# LevelShiftDAC.net
KiCad netlist of a schematic drawn in Altium Designer
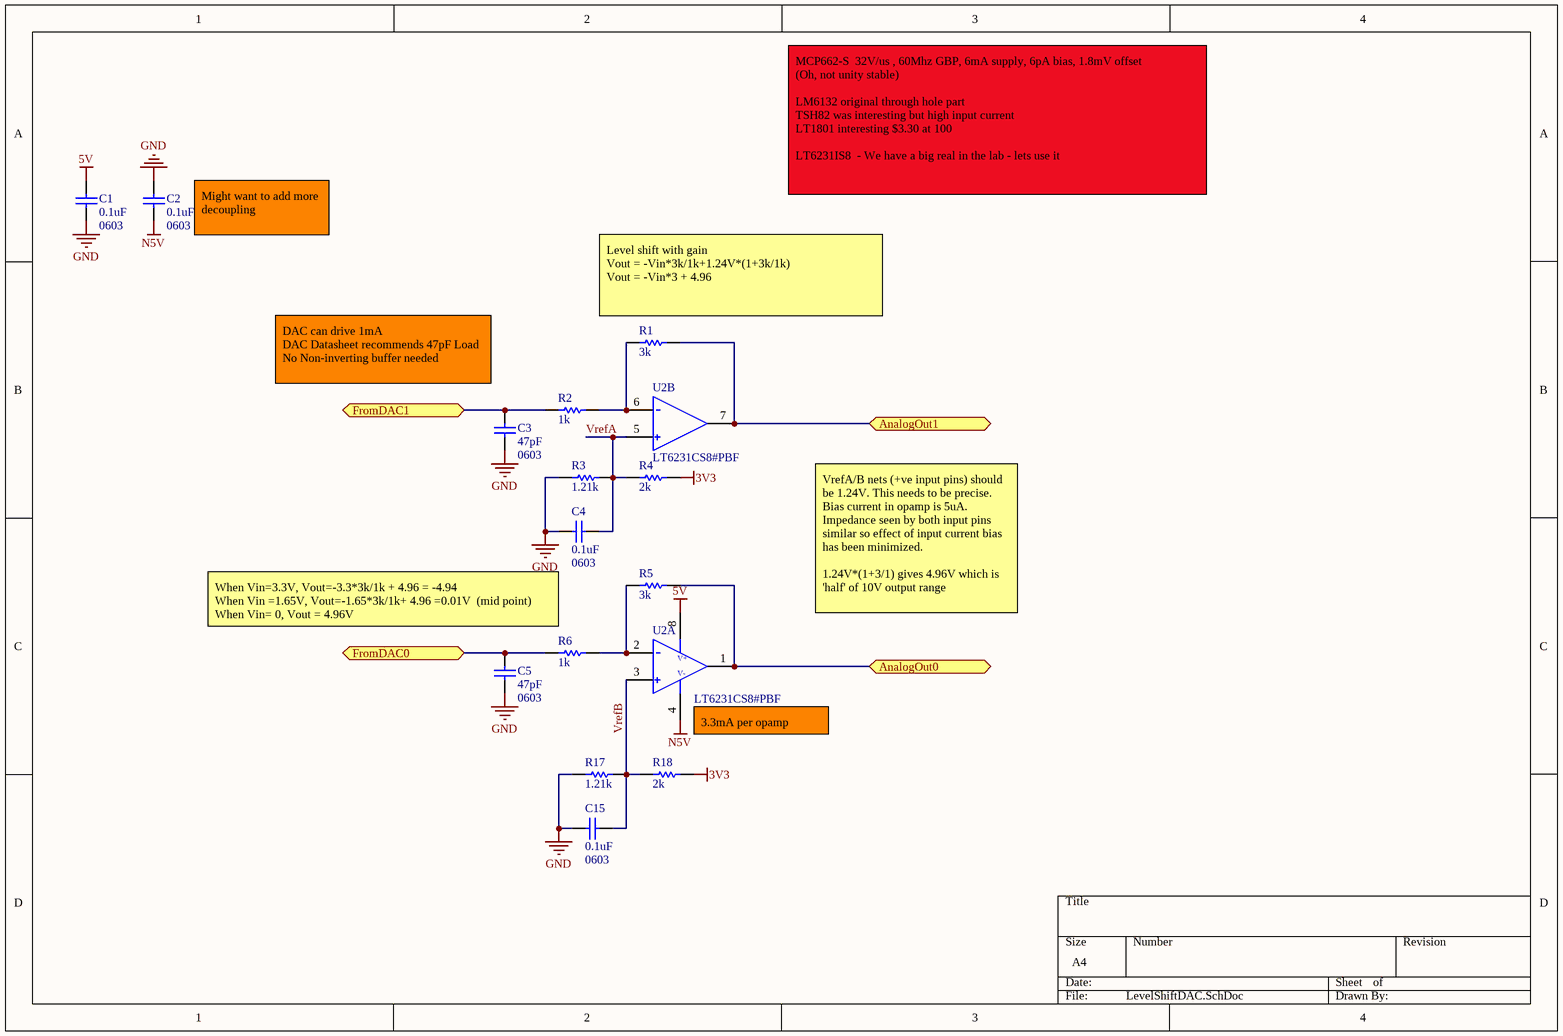
[diagram p0: LevelShiftDAC.SchDoc]

(export (version "E")
  (design (tool "Eeschema 10.0.6"))
  (components
    (comp (ref "C1")
      (value "0.1uF")
      (footprint "0603")
      (description "Capacitor, Ceramic, 0603")
      (fields
        (field (name "MANUFACTURER") "Samsung Electro-Mechanics")
        (field (name "MANUFACTURERS PART NUMBER") "CL10A104KA8NNNC")
      )
      (libsource (lib "projectlibrary") (part "Cap0603"))
    )
    (comp (ref "C2")
      (value "0.1uF")
      (footprint "0603")
      (description "Capacitor, Ceramic, 0603")
      (fields
        (field (name "MANUFACTURER") "Samsung Electro-Mechanics")
        (field (name "MANUFACTURERS PART NUMBER") "CL10A104KA8NNNC")
      )
      (libsource (lib "projectlibrary") (part "Cap0603"))
    )
    (comp (ref "C3")
      (value "47pF")
      (footprint "0603")
      (description "Capacitor, Ceramic, 0603")
      (fields
        (field (name "MANUFACTURER") "Wurth Electronics Inc.")
        (field (name "MANUFACTURERS PART NUMBER") "885012006021")
      )
      (libsource (lib "projectlibrary") (part "Cap0603"))
    )
    (comp (ref "C4")
      (value "0.1uF")
      (footprint "0603")
      (description "Capacitor, Ceramic, 0603")
      (fields
        (field (name "MANUFACTURER") "Samsung Electro-Mechanics")
        (field (name "MANUFACTURERS PART NUMBER") "CL10A104KA8NNNC")
      )
      (libsource (lib "projectlibrary") (part "Cap0603"))
    )
    (comp (ref "C5")
      (value "47pF")
      (footprint "0603")
      (description "Capacitor, Ceramic, 0603")
      (fields
        (field (name "MANUFACTURER") "Wurth Electronics Inc.")
        (field (name "MANUFACTURERS PART NUMBER") "885012006021")
      )
      (libsource (lib "projectlibrary") (part "Cap0603"))
    )
    (comp (ref "C15")
      (value "0.1uF")
      (footprint "0603")
      (description "Capacitor, Ceramic, 0603")
      (fields
        (field (name "MANUFACTURER") "Samsung Electro-Mechanics")
        (field (name "MANUFACTURERS PART NUMBER") "CL10A104KA8NNNC")
      )
      (libsource (lib "projectlibrary") (part "Cap0603"))
    )
    (comp (ref "R1")
      (value "3k")
      (footprint "0603")
      (description "Resistor")
      (fields
        (field (name "MANUFACTURER") "Vishay Dale")
        (field (name "MANUFACTURERS PART NUMBER") "CRCW06033K00FKEAC")
      )
      (libsource (lib "projectlibrary") (part "Res0603"))
    )
    (comp (ref "R2")
      (value "1k")
      (footprint "0603")
      (description "Resistor")
      (fields
        (field (name "MANUFACTURER") "Yageo")
        (field (name "MANUFACTURERS PART NUMBER") "RC0603FR-071KL")
      )
      (libsource (lib "projectlibrary") (part "Res0603"))
    )
    (comp (ref "R3")
      (value "1.21k")
      (footprint "0603")
      (description "Resistor")
      (fields
        (field (name "MANUFACTURER") "Yageo")
        (field (name "MANUFACTURERS PART NUMBER") "RMCF0603FT1K21")
      )
      (libsource (lib "projectlibrary") (part "Res0603"))
    )
    (comp (ref "R4")
      (value "2k")
      (footprint "0603")
      (description "Resistor")
      (fields
        (field (name "MANUFACTURER") "Vishay Dale")
        (field (name "MANUFACTURERS PART NUMBER") "CRCW06032K00FKEAC")
      )
      (libsource (lib "projectlibrary") (part "Res0603"))
    )
    (comp (ref "R5")
      (value "3k")
      (footprint "0603")
      (description "Resistor")
      (fields
        (field (name "MANUFACTURER") "Vishay Dale")
        (field (name "MANUFACTURERS PART NUMBER") "CRCW06033K00FKEAC")
      )
      (libsource (lib "projectlibrary") (part "Res0603"))
    )
    (comp (ref "R6")
      (value "1k")
      (footprint "0603")
      (description "Resistor")
      (fields
        (field (name "MANUFACTURER") "Yageo")
        (field (name "MANUFACTURERS PART NUMBER") "RC0603FR-071KL")
      )
      (libsource (lib "projectlibrary") (part "Res0603"))
    )
    (comp (ref "R17")
      (value "1.21k")
      (footprint "0603")
      (description "Resistor")
      (fields
        (field (name "MANUFACTURER") "Yageo")
        (field (name "MANUFACTURERS PART NUMBER") "RMCF0603FT1K21")
      )
      (libsource (lib "projectlibrary") (part "Res0603"))
    )
    (comp (ref "R18")
      (value "2k")
      (footprint "0603")
      (description "Resistor")
      (fields
        (field (name "MANUFACTURER") "Vishay Dale")
        (field (name "MANUFACTURERS PART NUMBER") "CRCW06032K00FKEAC")
      )
      (libsource (lib "projectlibrary") (part "Res0603"))
    )
    (comp (ref "U2")
      (value "LT6231CS8#PBF")
      (footprint "SO8")
      (description "Dual R-R Opamp Soic 8 215Mhz GBP")
      (fields
        (field (name "MANUFACTURERS PART NUMBER") "LT6231CS8")
        (field (name "MANUFACTURER") "Linear Technology/Analog Devices")
      )
      (libsource (lib "projectlibrary") (part "TSH82IYDT"))
    )
  )
  (nets
    (net (code "1") (name "/AnalogOut0") (class "Default")
      (node (ref "R5") (pin "2") (pinfunction "2_2") (pintype "passive"))
      (node (ref "U2") (pin "1") (pinfunction "Out_1") (pintype "passive"))
    )
    (net (code "2") (name "/AnalogOut1") (class "Default")
      (node (ref "R1") (pin "2") (pinfunction "2_2") (pintype "passive"))
      (node (ref "U2") (pin "7") (pinfunction "Out_7") (pintype "passive"))
    )
    (net (code "3") (name "/FromDAC0") (class "Default")
      (node (ref "C5") (pin "2") (pinfunction "2_2") (pintype "passive"))
      (node (ref "R6") (pin "1") (pinfunction "1_1") (pintype "passive"))
    )
    (net (code "4") (name "/FromDAC1") (class "Default")
      (node (ref "C3") (pin "2") (pinfunction "2_2") (pintype "passive"))
      (node (ref "R2") (pin "1") (pinfunction "1_1") (pintype "passive"))
    )
    (net (code "5") (name "/VrefA") (class "Default")
      (node (ref "C4") (pin "2") (pinfunction "2_2") (pintype "passive"))
      (node (ref "R3") (pin "2") (pinfunction "2_2") (pintype "passive"))
      (node (ref "R4") (pin "1") (pinfunction "1_1") (pintype "passive"))
      (node (ref "U2") (pin "5") (pinfunction "IN+_5") (pintype "passive"))
    )
    (net (code "6") (name "/VrefB") (class "Default")
      (node (ref "C15") (pin "2") (pinfunction "2_2") (pintype "passive"))
      (node (ref "R17") (pin "2") (pinfunction "2_2") (pintype "passive"))
      (node (ref "R18") (pin "1") (pinfunction "1_1") (pintype "passive"))
      (node (ref "U2") (pin "3") (pinfunction "IN+_3") (pintype "passive"))
    )
    (net (code "7") (name "3V3") (class "Default")
      (node (ref "R18") (pin "2") (pinfunction "2_2") (pintype "passive"))
      (node (ref "R4") (pin "2") (pinfunction "2_2") (pintype "passive"))
    )
    (net (code "8") (name "5V") (class "Default")
      (node (ref "C1") (pin "2") (pinfunction "2_2") (pintype "passive"))
      (node (ref "U2") (pin "8") (pinfunction "V+_8") (pintype "power_in"))
    )
    (net (code "9") (name "GND") (class "Default")
      (node (ref "C1") (pin "1") (pinfunction "1_1") (pintype "passive"))
      (node (ref "C15") (pin "1") (pinfunction "1_1") (pintype "passive"))
      (node (ref "C2") (pin "2") (pinfunction "2_2") (pintype "passive"))
      (node (ref "C3") (pin "1") (pinfunction "1_1") (pintype "passive"))
      (node (ref "C4") (pin "1") (pinfunction "1_1") (pintype "passive"))
      (node (ref "C5") (pin "1") (pinfunction "1_1") (pintype "passive"))
      (node (ref "R17") (pin "1") (pinfunction "1_1") (pintype "passive"))
      (node (ref "R3") (pin "1") (pinfunction "1_1") (pintype "passive"))
    )
    (net (code "10") (name "N5V") (class "Default")
      (node (ref "C2") (pin "1") (pinfunction "1_1") (pintype "passive"))
      (node (ref "U2") (pin "4") (pinfunction "V-_4") (pintype "power_in"))
    )
    (net (code "11") (name "Net-(U2A-IN-)") (class "Default")
      (node (ref "R5") (pin "1") (pinfunction "1_1") (pintype "passive"))
      (node (ref "R6") (pin "2") (pinfunction "2_2") (pintype "passive"))
      (node (ref "U2") (pin "2") (pinfunction "IN-_2") (pintype "passive"))
    )
    (net (code "12") (name "Net-(U2B-IN-)") (class "Default")
      (node (ref "R1") (pin "1") (pinfunction "1_1") (pintype "passive"))
      (node (ref "R2") (pin "2") (pinfunction "2_2") (pintype "passive"))
      (node (ref "U2") (pin "6") (pinfunction "IN-_6") (pintype "passive"))
    )
  )
)
